# Power.net
KiCad netlist of a schematic drawn in Altium Designer
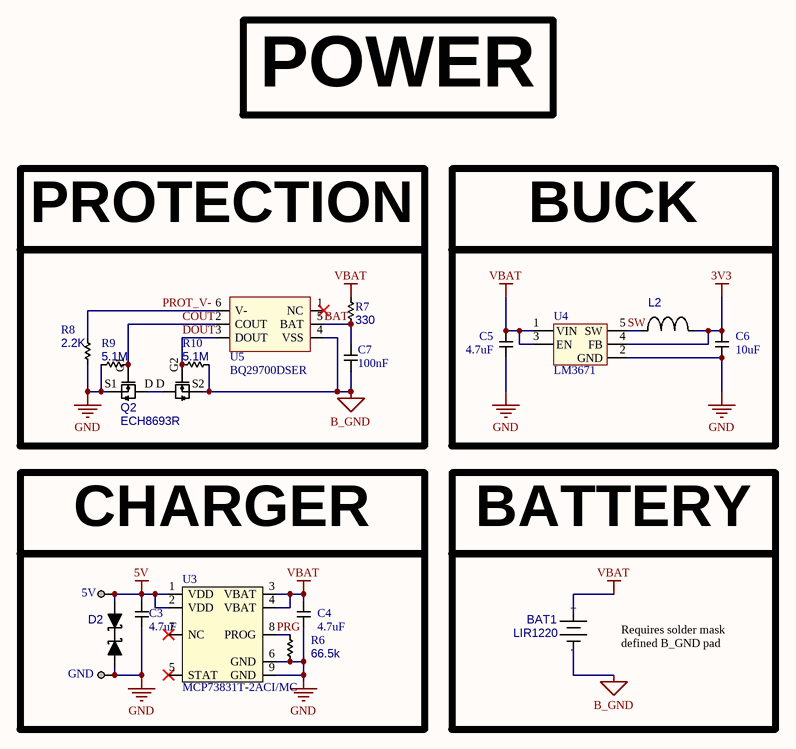
[diagram p0: Power.SchDoc]

(export (version "E")
  (design (tool "Eeschema 10.0.6"))
  (components
    (comp (ref "5V")
      (value "0.1\" Pad")
      (footprint "0.1\" Pad")
      (libsource (lib "smLib") (part "0.1{dblquote} Pad"))
    )
    (comp (ref "BAT1")
      (value "LIR1220")
      (footprint "LIR1220")
      (description "LIR1220 Battery")
      (libsource (lib "smLib") (part "LIR1220 Batter"))
    )
    (comp (ref "C3")
      (value "4.7uF")
      (footprint "CAP_0402_HIGH")
      (description "0402 Capacitor")
      (libsource (lib "smLib") (part "Capacitor_0402"))
    )
    (comp (ref "C4")
      (value "4.7uF")
      (footprint "CAP_0402_HIGH")
      (description "0402 Capacitor")
      (libsource (lib "smLib") (part "Capacitor_0402"))
    )
    (comp (ref "C5")
      (value "4.7uF")
      (footprint "CAP_0402_HIGH")
      (description "0402 Capacitor")
      (libsource (lib "smLib") (part "Capacitor_0402"))
    )
    (comp (ref "C6")
      (value "10uF")
      (footprint "CAP_0402_HIGH")
      (description "0402 Capacitor")
      (libsource (lib "smLib") (part "Capacitor_0402"))
    )
    (comp (ref "C7")
      (value "100nF")
      (footprint "CAP_0402_HIGH")
      (description "0402 Capacitor")
      (libsource (lib "smLib") (part "Capacitor_0402"))
    )
    (comp (ref "D2")
      (value "D5V0L1B2LP4-7B")
      (footprint "D5V0L1B2LP4-7B")
      (description "D5V0L1B2LP4-7B 14V Clamp 6A (8/20µs) Ipp Tvs Diode Surface Mount X2-DFN1006-2")
      (libsource (lib "smLib") (part "D5V0L1B2LP4-7B"))
    )
    (comp (ref "GND")
      (value "0.1\" Pad")
      (footprint "0.1\" Pad")
      (libsource (lib "smLib") (part "0.1{dblquote} Pad"))
    )
    (comp (ref "L2")
      (value "CIGT201610EH2R2MNE")
      (footprint "CIGT201610EH2R2MNE")
      (description "CIGT201610EH2R2MNE 2.2µH Unshielded Thin Film Inductor 2.5A 87mOhm Max 0806 (2016 Metric)")
      (libsource (lib "smLib") (part "CIGT201610EH2R2MNE"))
    )
    (comp (ref "Q2")
      (value "ECH8693R")
      (footprint "ECH8693R")
      (description "Mosfet Array 2 N-Channel (Dual) Common Drain 24V 14A 1.4W Surface Mount SOT-28FL/ECH8")
      (libsource (lib "smLib") (part "ECH8693R"))
    )
    (comp (ref "R6")
      (value "66.5k")
      (footprint "RES_0402_HIGH")
      (description "0402 Resistor")
      (libsource (lib "smLib") (part "Resistor_0402"))
    )
    (comp (ref "R7")
      (value "330")
      (footprint "RES_0402_HIGH")
      (description "0402 Resistor")
      (libsource (lib "smLib") (part "Resistor_0402"))
    )
    (comp (ref "R8")
      (value "2.2K")
      (footprint "RES_0402_HIGH")
      (description "0402 Resistor")
      (libsource (lib "smLib") (part "Resistor_0402"))
    )
    (comp (ref "R9")
      (value "5.1M")
      (footprint "RES_0402_HIGH")
      (description "0402 Resistor")
      (libsource (lib "smLib") (part "Resistor_0402"))
    )
    (comp (ref "R10")
      (value "5.1M")
      (footprint "RES_0402_HIGH")
      (description "0402 Resistor")
      (libsource (lib "smLib") (part "Resistor_0402"))
    )
    (comp (ref "U3")
      (value "MCP73831T-2ACI/MC")
      (footprint "MCP73831T-2ACI/MC")
      (description "MCP73831T-2ACI/MC Charger IC Lithium-Ion/Polymer")
      (libsource (lib "smLib") (part "MCP73831T-2ACI/MC"))
    )
    (comp (ref "U4")
      (value "LM3671")
      (footprint "LM3671-BGA")
      (description "LM3671 IC REG BUCK 3.3V 0.6A SYNC 5USMD")
      (libsource (lib "smLib") (part "LM3671"))
    )
    (comp (ref "U5")
      (value "BQ29700DSER")
      (footprint "BQ29700DSER")
      (description "Battery Battery Protection IC Lithium-Ion/Polymer 6-WSON (1.5x1.5)")
      (libsource (lib "smLib") (part "BQ29700DSER"))
    )
  )
  (nets
    (net (code "1") (name "/BAT") (class "Default")
      (node (ref "C7") (pin "2") (pinfunction "2_2") (pintype "passive"))
      (node (ref "R7") (pin "2") (pinfunction "2_2") (pintype "passive"))
      (node (ref "U5") (pin "5") (pinfunction "BAT_5") (pintype "passive"))
    )
    (net (code "2") (name "/COUT") (class "Default")
      (node (ref "Q2") (pin "G1") (pinfunction "G_G1") (pintype "passive"))
      (node (ref "R9") (pin "1") (pinfunction "1_1") (pintype "passive"))
      (node (ref "U5") (pin "2") (pinfunction "COUT_2") (pintype "passive"))
    )
    (net (code "3") (name "/DOUT") (class "Default")
      (node (ref "Q2") (pin "G2") (pinfunction "G_G2") (pintype "passive"))
      (node (ref "R10") (pin "2") (pinfunction "2_2") (pintype "passive"))
      (node (ref "U5") (pin "3") (pinfunction "DOUT_3") (pintype "passive"))
    )
    (net (code "4") (name "/PRG") (class "Default")
      (node (ref "R6") (pin "1") (pinfunction "1_1") (pintype "passive"))
      (node (ref "U3") (pin "8") (pinfunction "PROG_8") (pintype "passive"))
    )
    (net (code "5") (name "/PROT_V-") (class "Default")
      (node (ref "R8") (pin "2") (pinfunction "2_2") (pintype "passive"))
      (node (ref "U5") (pin "6") (pinfunction "V-_6") (pintype "passive"))
    )
    (net (code "6") (name "/SW") (class "Default")
      (node (ref "L2") (pin "1") (pinfunction "1_1") (pintype "passive"))
      (node (ref "U4") (pin "5") (pinfunction "SW_5") (pintype "passive"))
    )
    (net (code "7") (name "3V3") (class "Default")
      (node (ref "C6") (pin "2") (pinfunction "2_2") (pintype "passive"))
      (node (ref "L2") (pin "2") (pinfunction "2_2") (pintype "passive"))
      (node (ref "U4") (pin "4") (pinfunction "FB_4") (pintype "passive"))
    )
    (net (code "8") (name "5V") (class "Default")
      (node (ref "5V") (pin "1") (pinfunction "1_1") (pintype "passive"))
      (node (ref "C3") (pin "2") (pinfunction "2_2") (pintype "passive"))
      (node (ref "D2") (pin "1") (pinfunction "1_1") (pintype "passive"))
      (node (ref "U3") (pin "1") (pinfunction "VDD_1") (pintype "passive"))
      (node (ref "U3") (pin "2") (pinfunction "VDD_2") (pintype "passive"))
    )
    (net (code "9") (name "B_GND") (class "Default")
      (node (ref "C7") (pin "1") (pinfunction "1_1") (pintype "passive"))
      (node (ref "Q2") (pin "S2") (pinfunction "S_S2") (pintype "passive"))
      (node (ref "R10") (pin "1") (pinfunction "1_1") (pintype "passive"))
      (node (ref "U5") (pin "4") (pinfunction "VSS_4") (pintype "passive"))
    )
    (net (code "10") (name "GND") (class "Default")
      (node (ref "C3") (pin "1") (pinfunction "1_1") (pintype "passive"))
      (node (ref "C4") (pin "1") (pinfunction "1_1") (pintype "passive"))
      (node (ref "C5") (pin "1") (pinfunction "1_1") (pintype "passive"))
      (node (ref "C6") (pin "1") (pinfunction "1_1") (pintype "passive"))
      (node (ref "D2") (pin "2") (pinfunction "2_2") (pintype "passive"))
      (node (ref "GND") (pin "1") (pinfunction "1_1") (pintype "passive"))
      (node (ref "Q2") (pin "S1") (pinfunction "S_S1") (pintype "passive"))
      (node (ref "R6") (pin "2") (pinfunction "2_2") (pintype "passive"))
      (node (ref "R8") (pin "1") (pinfunction "1_1") (pintype "passive"))
      (node (ref "R9") (pin "2") (pinfunction "2_2") (pintype "passive"))
      (node (ref "U3") (pin "6") (pinfunction "GND_6") (pintype "passive"))
      (node (ref "U3") (pin "9") (pinfunction "GND_9") (pintype "passive"))
      (node (ref "U4") (pin "2") (pinfunction "GND_2") (pintype "passive"))
    )
    (net (code "11") (name "Net-(Q2-PadD)") (class "Default")
      (node (ref "Q2") (pin "D") (pinfunction "D_D") (pintype "passive"))
    )
    (net (code "12") (name "VBAT") (class "Default")
      (node (ref "BAT1") (pin "1") (pinfunction "+_1") (pintype "passive"))
      (node (ref "C4") (pin "2") (pinfunction "2_2") (pintype "passive"))
      (node (ref "C5") (pin "2") (pinfunction "2_2") (pintype "passive"))
      (node (ref "R7") (pin "1") (pinfunction "1_1") (pintype "passive"))
      (node (ref "U3") (pin "3") (pinfunction "VBAT_3") (pintype "passive"))
      (node (ref "U3") (pin "4") (pinfunction "VBAT_4") (pintype "passive"))
      (node (ref "U4") (pin "1") (pinfunction "VIN_1") (pintype "passive"))
      (node (ref "U4") (pin "3") (pinfunction "EN_3") (pintype "passive"))
    )
    (net (code "13") (name "unconnected-(U3-NC-Pad7)") (class "Default")
      (node (ref "U3") (pin "7") (pinfunction "NC_7") (pintype "passive+no_connect"))
    )
    (net (code "14") (name "unconnected-(U3-STAT-Pad5)") (class "Default")
      (node (ref "U3") (pin "5") (pinfunction "STAT_5") (pintype "passive+no_connect"))
    )
    (net (code "15") (name "unconnected-(U5-NC-Pad1)") (class "Default")
      (node (ref "U5") (pin "1") (pinfunction "NC_1") (pintype "passive+no_connect"))
    )
  )
)
